# kicker.net
KiCad netlist of a schematic drawn in EAGLE
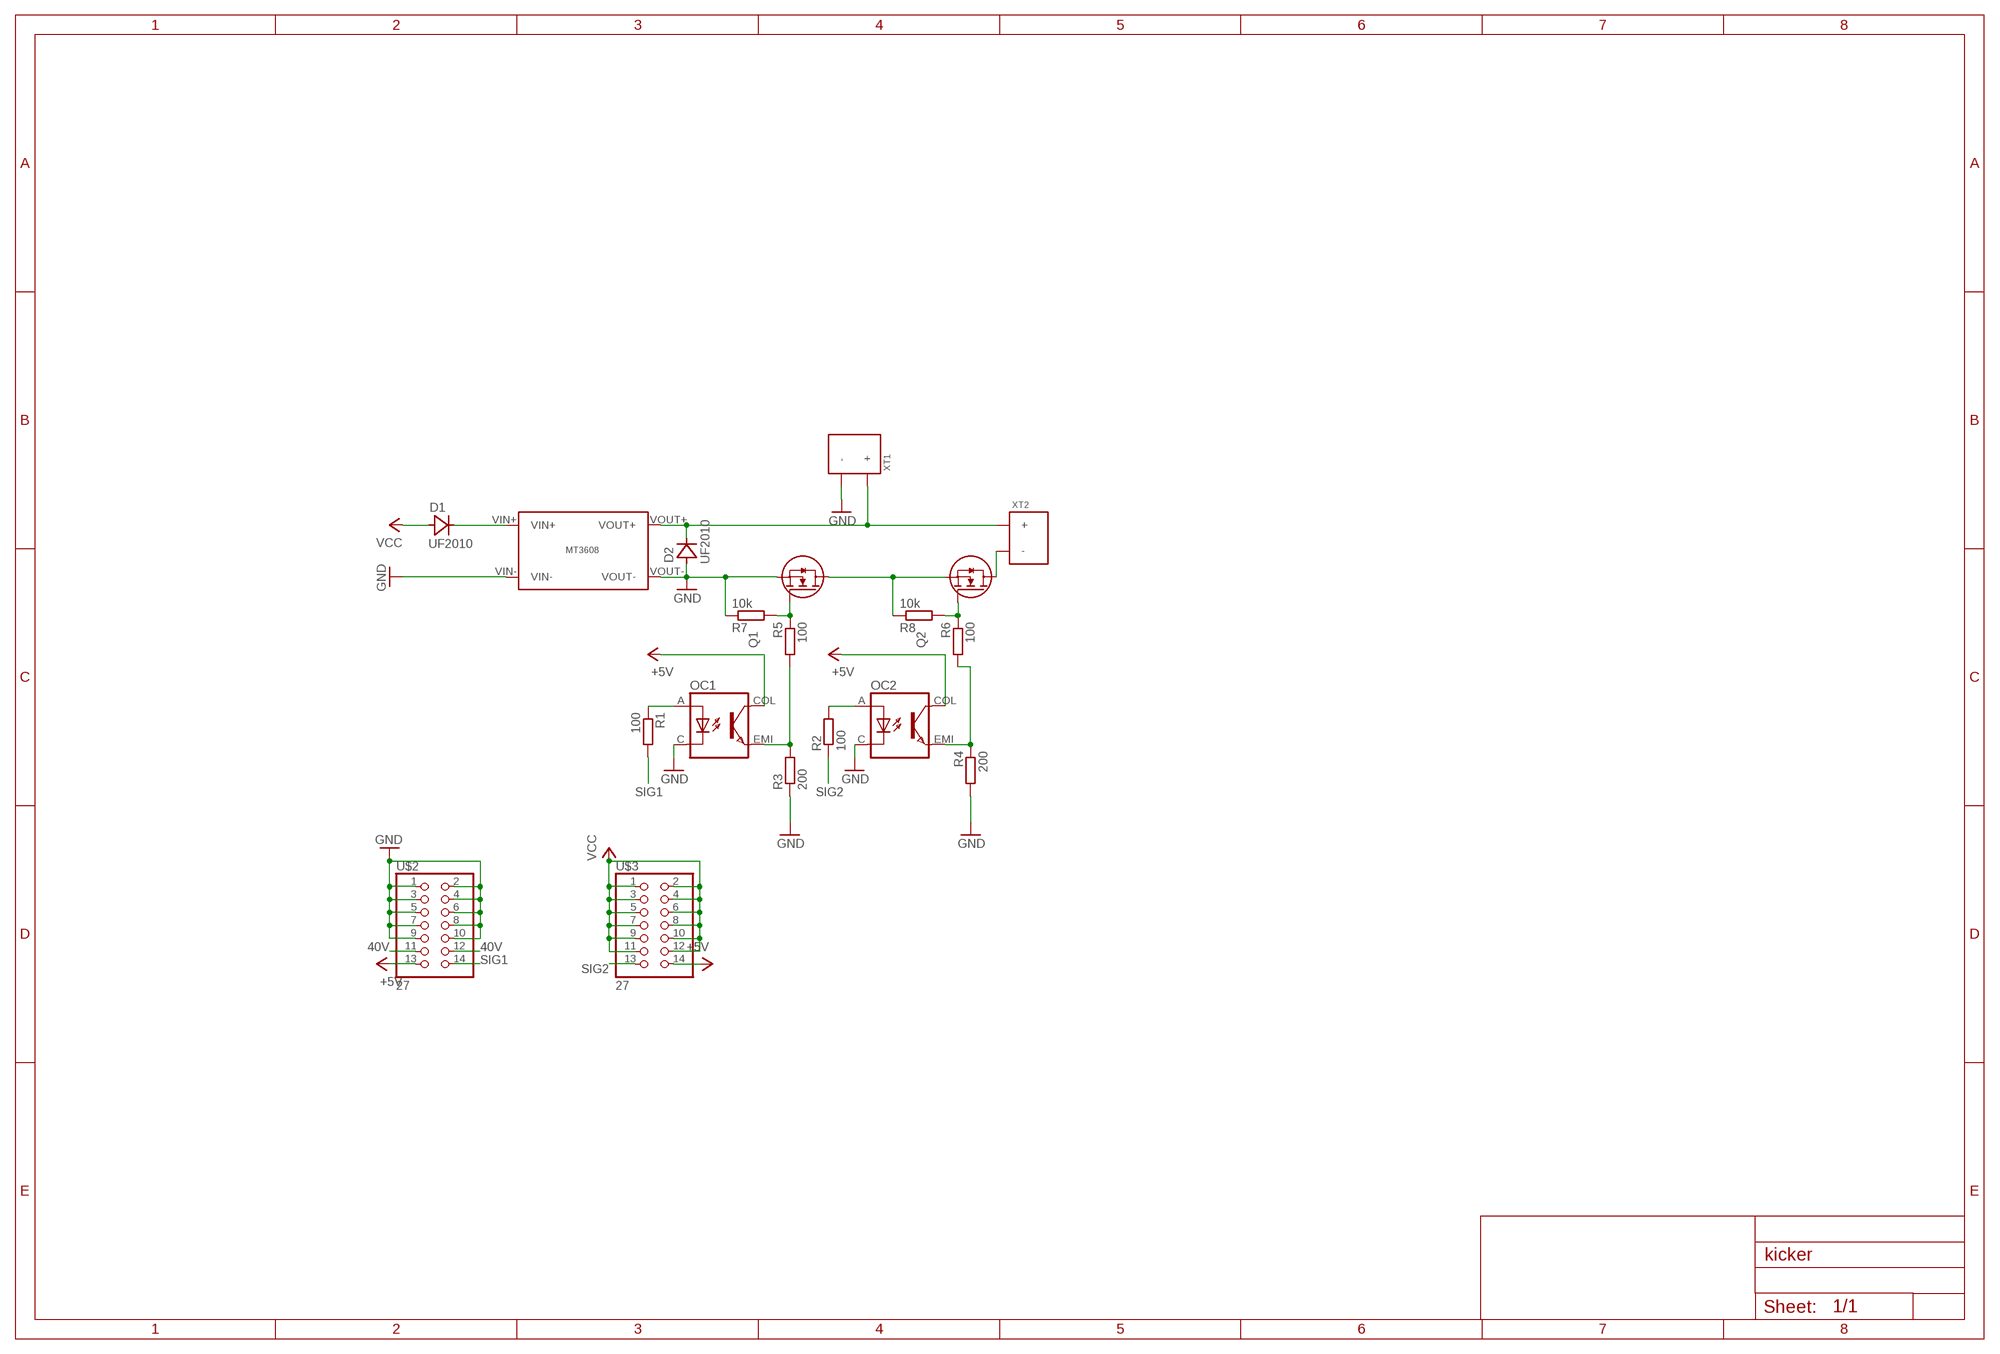
[diagram p0: schematic, sheet 1]

(export (version "E")
  (design (tool "Eeschema 10.0.6"))
  (components
    (comp (ref "D1")
      (value "UF2010")
      (footprint "eagle-import:UF2010")
      (libsource (lib "eagle-import") (part "UF2010"))
    )
    (comp (ref "D2")
      (value "UF2010")
      (footprint "eagle-import:UF2010")
      (libsource (lib "eagle-import") (part "UF2010"))
    )
    (comp (ref "OC1")
      (value "TL293(GB)")
      (footprint "eagle-import:SOIC127P700X230-4N")
      (libsource (lib "eagle-import") (part "TL293(GB)"))
    )
    (comp (ref "OC2")
      (value "TL293(GB)")
      (footprint "eagle-import:SOIC127P700X230-4N")
      (libsource (lib "eagle-import") (part "TL293(GB)"))
    )
    (comp (ref "Q1")
      (value "NP52N06SLG")
      (footprint "eagle-import:TO230P1040X230-3N")
      (libsource (lib "eagle-import") (part "NP52N06SLG"))
    )
    (comp (ref "Q2")
      (value "NP52N06SLG")
      (footprint "eagle-import:TO230P1040X230-3N")
      (libsource (lib "eagle-import") (part "NP52N06SLG"))
    )
    (comp (ref "R1")
      (value "100")
      (footprint "eagle-import:R0603")
      (libsource (lib "eagle-import") (part "R-EU_R0603"))
    )
    (comp (ref "R2")
      (value "100")
      (footprint "eagle-import:R0603")
      (libsource (lib "eagle-import") (part "R-EU_R0603"))
    )
    (comp (ref "R3")
      (value "200")
      (footprint "eagle-import:R0603")
      (libsource (lib "eagle-import") (part "R-EU_R0603"))
    )
    (comp (ref "R4")
      (value "200")
      (footprint "eagle-import:R0603")
      (libsource (lib "eagle-import") (part "R-EU_R0603"))
    )
    (comp (ref "R5")
      (value "100")
      (footprint "eagle-import:R0603")
      (libsource (lib "eagle-import") (part "R-EU_R0603"))
    )
    (comp (ref "R6")
      (value "100")
      (footprint "eagle-import:R0603")
      (libsource (lib "eagle-import") (part "R-EU_R0603"))
    )
    (comp (ref "R7")
      (value "10k")
      (footprint "eagle-import:R0603")
      (libsource (lib "eagle-import") (part "R-EU_R0603"))
    )
    (comp (ref "R8")
      (value "10k")
      (footprint "eagle-import:R0603")
      (libsource (lib "eagle-import") (part "R-EU_R0603"))
    )
    (comp (ref "U$1")
      (value "MT3608")
      (footprint "eagle-import:MT3608")
      (libsource (lib "eagle-import") (part "MT3608"))
    )
    (comp (ref "U$2")
      (value "27")
      (footprint "eagle-import:2_7")
      (libsource (lib "eagle-import") (part "27"))
    )
    (comp (ref "U$3")
      (value "27")
      (footprint "eagle-import:2_7")
      (libsource (lib "eagle-import") (part "27"))
    )
    (comp (ref "XT1")
      (value "XT30PW-F")
      (footprint "eagle-import:XT30PW-F")
      (libsource (lib "eagle-import") (part "XT30PW-F"))
    )
    (comp (ref "XT2")
      (value "XT30PW-F")
      (footprint "eagle-import:XT30PW-F")
      (libsource (lib "eagle-import") (part "XT30PW-F"))
    )
  )
  (nets
    (net (code "1") (name "+5V") (class "Default")
      (node (ref "OC1") (pin "COL") (pinfunction "COL_COL") (pintype "passive"))
      (node (ref "OC2") (pin "COL") (pinfunction "COL_COL") (pintype "passive"))
      (node (ref "U$2") (pin "13") (pinfunction "13_13") (pintype "passive"))
      (node (ref "U$3") (pin "14") (pinfunction "14_14") (pintype "passive"))
    )
    (net (code "2") (name "/40V") (class "Default")
      (node (ref "D2") (pin "C") (pinfunction "C_C") (pintype "passive"))
      (node (ref "U$1") (pin "VOUT+") (pinfunction "VOUT+_VOUT+") (pintype "bidirectional"))
      (node (ref "U$2") (pin "11") (pinfunction "11_11") (pintype "passive"))
      (node (ref "U$2") (pin "12") (pinfunction "12_12") (pintype "passive"))
      (node (ref "XT1") (pin "+") (pinfunction "+_+") (pintype "bidirectional"))
      (node (ref "XT2") (pin "+") (pinfunction "+_+") (pintype "bidirectional"))
    )
    (net (code "3") (name "/SIG1") (class "Default")
      (node (ref "R1") (pin "2") (pinfunction "2_2") (pintype "passive"))
      (node (ref "U$2") (pin "14") (pinfunction "14_14") (pintype "passive"))
    )
    (net (code "4") (name "/SIG2") (class "Default")
      (node (ref "R2") (pin "1") (pinfunction "1_1") (pintype "passive"))
      (node (ref "U$3") (pin "13") (pinfunction "13_13") (pintype "passive"))
    )
    (net (code "5") (name "GND") (class "Default")
      (node (ref "D2") (pin "A") (pinfunction "A_A") (pintype "passive"))
      (node (ref "OC1") (pin "C") (pinfunction "C_C") (pintype "passive"))
      (node (ref "OC2") (pin "C") (pinfunction "C_C") (pintype "passive"))
      (node (ref "Q1") (pin "S") (pinfunction "S_S") (pintype "passive"))
      (node (ref "R3") (pin "1") (pinfunction "1_1") (pintype "passive"))
      (node (ref "R4") (pin "2") (pinfunction "2_2") (pintype "passive"))
      (node (ref "R7") (pin "1") (pinfunction "1_1") (pintype "passive"))
      (node (ref "U$1") (pin "VIN-") (pinfunction "VIN-_VIN-") (pintype "bidirectional"))
      (node (ref "U$1") (pin "VOUT-") (pinfunction "VOUT-_VOUT-") (pintype "bidirectional"))
      (node (ref "U$2") (pin "1") (pinfunction "1_1") (pintype "passive"))
      (node (ref "U$2") (pin "10") (pinfunction "10_10") (pintype "passive"))
      (node (ref "U$2") (pin "2") (pinfunction "2_2") (pintype "passive"))
      (node (ref "U$2") (pin "3") (pinfunction "3_3") (pintype "passive"))
      (node (ref "U$2") (pin "4") (pinfunction "4_4") (pintype "passive"))
      (node (ref "U$2") (pin "5") (pinfunction "5_5") (pintype "passive"))
      (node (ref "U$2") (pin "6") (pinfunction "6_6") (pintype "passive"))
      (node (ref "U$2") (pin "7") (pinfunction "7_7") (pintype "passive"))
      (node (ref "U$2") (pin "8") (pinfunction "8_8") (pintype "passive"))
      (node (ref "U$2") (pin "9") (pinfunction "9_9") (pintype "passive"))
      (node (ref "XT1") (pin "-") (pinfunction "-_-") (pintype "bidirectional"))
    )
    (net (code "6") (name "Net-(D1-PadC)") (class "Default")
      (node (ref "D1") (pin "C") (pinfunction "C_C") (pintype "passive"))
      (node (ref "U$1") (pin "VIN+") (pinfunction "VIN+_VIN+") (pintype "bidirectional"))
    )
    (net (code "7") (name "Net-(OC1-PadA)") (class "Default")
      (node (ref "OC1") (pin "A") (pinfunction "A_A") (pintype "passive"))
      (node (ref "R1") (pin "1") (pinfunction "1_1") (pintype "passive"))
    )
    (net (code "8") (name "Net-(OC1-PadEMI)") (class "Default")
      (node (ref "OC1") (pin "EMI") (pinfunction "EMI_EMI") (pintype "passive"))
      (node (ref "R3") (pin "2") (pinfunction "2_2") (pintype "passive"))
      (node (ref "R5") (pin "2") (pinfunction "2_2") (pintype "passive"))
    )
    (net (code "9") (name "Net-(OC2-PadA)") (class "Default")
      (node (ref "OC2") (pin "A") (pinfunction "A_A") (pintype "passive"))
      (node (ref "R2") (pin "2") (pinfunction "2_2") (pintype "passive"))
    )
    (net (code "10") (name "Net-(OC2-PadEMI)") (class "Default")
      (node (ref "OC2") (pin "EMI") (pinfunction "EMI_EMI") (pintype "passive"))
      (node (ref "R4") (pin "1") (pinfunction "1_1") (pintype "passive"))
      (node (ref "R6") (pin "2") (pinfunction "2_2") (pintype "passive"))
    )
    (net (code "11") (name "Net-(Q1-PadD)") (class "Default")
      (node (ref "Q1") (pin "D") (pinfunction "D_D") (pintype "passive"))
      (node (ref "Q2") (pin "S") (pinfunction "S_S") (pintype "passive"))
      (node (ref "R8") (pin "1") (pinfunction "1_1") (pintype "passive"))
    )
    (net (code "12") (name "Net-(Q1-PadG)") (class "Default")
      (node (ref "Q1") (pin "G") (pinfunction "G_G") (pintype "passive"))
      (node (ref "R5") (pin "1") (pinfunction "1_1") (pintype "passive"))
      (node (ref "R7") (pin "2") (pinfunction "2_2") (pintype "passive"))
    )
    (net (code "13") (name "Net-(Q2-PadD)") (class "Default")
      (node (ref "Q2") (pin "D") (pinfunction "D_D") (pintype "passive"))
      (node (ref "XT2") (pin "-") (pinfunction "-_-") (pintype "bidirectional"))
    )
    (net (code "14") (name "Net-(Q2-PadG)") (class "Default")
      (node (ref "Q2") (pin "G") (pinfunction "G_G") (pintype "passive"))
      (node (ref "R6") (pin "1") (pinfunction "1_1") (pintype "passive"))
      (node (ref "R8") (pin "2") (pinfunction "2_2") (pintype "passive"))
    )
    (net (code "15") (name "VCC") (class "Default")
      (node (ref "D1") (pin "A") (pinfunction "A_A") (pintype "passive"))
      (node (ref "U$3") (pin "1") (pinfunction "1_1") (pintype "passive"))
      (node (ref "U$3") (pin "10") (pinfunction "10_10") (pintype "passive"))
      (node (ref "U$3") (pin "11") (pinfunction "11_11") (pintype "passive"))
      (node (ref "U$3") (pin "12") (pinfunction "12_12") (pintype "passive"))
      (node (ref "U$3") (pin "2") (pinfunction "2_2") (pintype "passive"))
      (node (ref "U$3") (pin "3") (pinfunction "3_3") (pintype "passive"))
      (node (ref "U$3") (pin "4") (pinfunction "4_4") (pintype "passive"))
      (node (ref "U$3") (pin "5") (pinfunction "5_5") (pintype "passive"))
      (node (ref "U$3") (pin "6") (pinfunction "6_6") (pintype "passive"))
      (node (ref "U$3") (pin "7") (pinfunction "7_7") (pintype "passive"))
      (node (ref "U$3") (pin "8") (pinfunction "8_8") (pintype "passive"))
      (node (ref "U$3") (pin "9") (pinfunction "9_9") (pintype "passive"))
    )
  )
)
